# STM32L152.net
KiCad netlist of a schematic drawn in Altium Designer
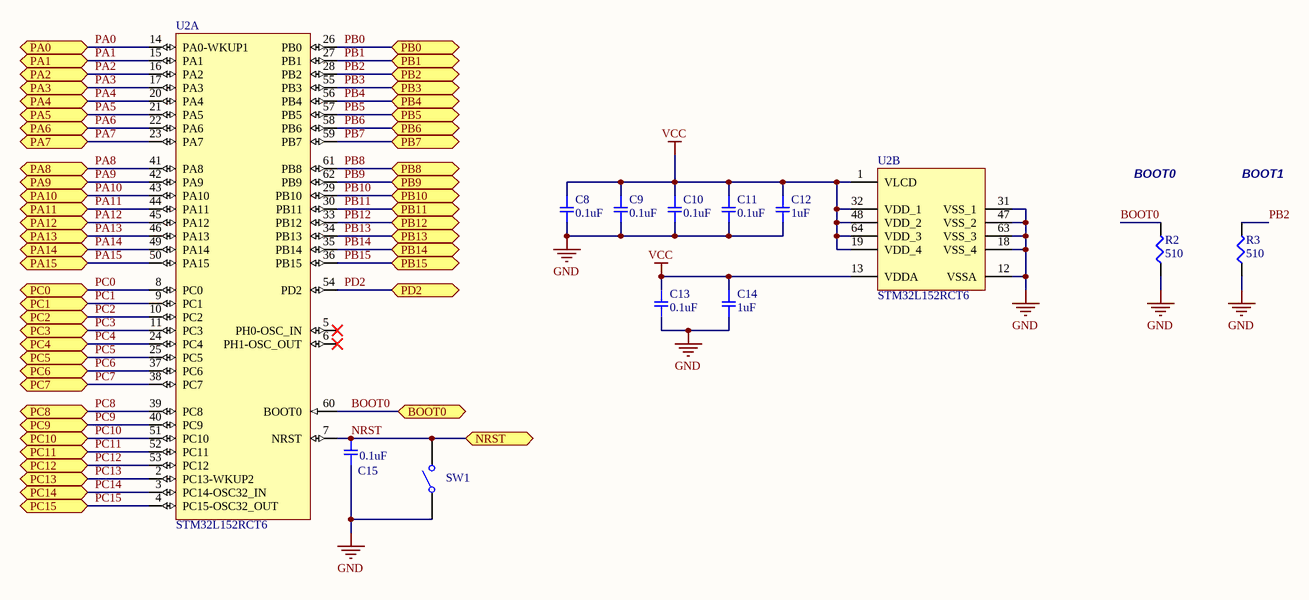
[diagram p0: STM32L152.SchDoc]

(export (version "E")
  (design (tool "Eeschema 10.0.6"))
  (components
    (comp (ref "C8")
      (value "0.1uF")
      (footprint "SMD-0805C")
      (description "CAP CER 0.1uF 50V X7T 0805")
      (fields
        (field (name "PART NUMBER") "GC321AD72E103KX01D")
        (field (name "MANUFACTURER") "Samsung Electro-Mechanics")
      )
      (libsource (lib "capacitor_0805") (part "CL21B104JBCNNNC"))
    )
    (comp (ref "C9")
      (value "0.1uF")
      (footprint "SMD-0805C")
      (description "CAP CER 0.1uF 50V X7T 0805")
      (fields
        (field (name "PART NUMBER") "GC321AD72E103KX01D")
        (field (name "MANUFACTURER") "Samsung Electro-Mechanics")
      )
      (libsource (lib "capacitor_0805") (part "CL21B104JBCNNNC"))
    )
    (comp (ref "C10")
      (value "0.1uF")
      (footprint "SMD-0805C")
      (description "CAP CER 0.1uF 50V X7T 0805")
      (fields
        (field (name "PART NUMBER") "GC321AD72E103KX01D")
        (field (name "MANUFACTURER") "Samsung Electro-Mechanics")
      )
      (libsource (lib "capacitor_0805") (part "CL21B104JBCNNNC"))
    )
    (comp (ref "C11")
      (value "0.1uF")
      (footprint "SMD-0805C")
      (description "CAP CER 0.1uF 50V X7T 0805")
      (fields
        (field (name "PART NUMBER") "GC321AD72E103KX01D")
        (field (name "MANUFACTURER") "Samsung Electro-Mechanics")
      )
      (libsource (lib "capacitor_0805") (part "CL21B104JBCNNNC"))
    )
    (comp (ref "C12")
      (value "1uF")
      (footprint "SMD-0805C")
      (description "CAP CER 1uF 16V X7T 0805")
      (fields
        (field (name "PART NUMBER") "CL21B105KOFNNNG")
        (field (name "MANUFACTURER") "Samsung Electro-Mechanics")
      )
      (libsource (lib "capacitor_0805") (part "CL21B105KOFNNNG"))
    )
    (comp (ref "C13")
      (value "0.1uF")
      (footprint "SMD-0805C")
      (description "CAP CER 0.1uF 50V X7T 0805")
      (fields
        (field (name "PART NUMBER") "GC321AD72E103KX01D")
        (field (name "MANUFACTURER") "Samsung Electro-Mechanics")
      )
      (libsource (lib "capacitor_0805") (part "CL21B104JBCNNNC"))
    )
    (comp (ref "C14")
      (value "1uF")
      (footprint "SMD-0805C")
      (description "CAP CER 1uF 16V X7T 0805")
      (fields
        (field (name "PART NUMBER") "CL21B105KOFNNNG")
        (field (name "MANUFACTURER") "Samsung Electro-Mechanics")
      )
      (libsource (lib "capacitor_0805") (part "CL21B105KOFNNNG"))
    )
    (comp (ref "C15")
      (value "0.1uF")
      (footprint "SMD-0805C")
      (description "CAP CER 0.1uF 50V X7T 0805")
      (fields
        (field (name "PART NUMBER") "GC321AD72E103KX01D")
        (field (name "MANUFACTURER") "Samsung Electro-Mechanics")
      )
      (libsource (lib "capacitor_0805") (part "CL21B104JBCNNNC"))
    )
    (comp (ref "R2")
      (value "510")
      (footprint "SMD-0805-RES")
      (description "RES SMD 510 OHM 5% 1/8W 0805")
      (fields (field (name "PART NUMBER") "ERJ-6GEYJ511V") (field (name "DIGI-KEY PART NUMBER") "P510ACT-ND"))
      (libsource (lib "Panasonic_ERJ_0805") (part "ERJ-6GEYJ511V"))
    )
    (comp (ref "R3")
      (value "510")
      (footprint "SMD-0805-RES")
      (description "RES SMD 510 OHM 5% 1/8W 0805")
      (fields (field (name "PART NUMBER") "ERJ-6GEYJ511V") (field (name "DIGI-KEY PART NUMBER") "P510ACT-ND"))
      (libsource (lib "Panasonic_ERJ_0805") (part "ERJ-6GEYJ511V"))
    )
    (comp (ref "SW1")
      (value "Switch_Tact")
      (footprint "Switch_Tact")
      (description "WS-TASV SMD Tact Switch 6.0X3.5 mm")
      (fields (field (name "PARTNUMBER") "434121050836"))
      (libsource (lib "Tesis") (part "Switch_Tact"))
    )
    (comp (ref "U2")
      (value "STM32L152RCT6")
      (footprint "STM-LQFP64_L")
      (fields (field (name "MANUFACTURER") "STMicroelectronics"))
      (libsource (lib "STMicroelectronics STM32 L1") (part "STM32L152RCT6"))
    )
  )
  (nets
    (net (code "1") (name "/BOOT0") (class "Default")
      (node (ref "R2") (pin "2") (pinfunction "2_2") (pintype "passive"))
      (node (ref "U2") (pin "60") (pinfunction "BOOT0_60") (pintype "input"))
    )
    (net (code "2") (name "/NRST") (class "Default")
      (node (ref "C15") (pin "1") (pinfunction "1_1") (pintype "passive"))
      (node (ref "SW1") (pin "2") (pinfunction "2_2") (pintype "passive"))
      (node (ref "U2") (pin "7") (pinfunction "NRST_7") (pintype "bidirectional"))
    )
    (net (code "3") (name "/PA0") (class "Default")
      (node (ref "U2") (pin "14") (pinfunction "PA0-WKUP1_14") (pintype "bidirectional"))
    )
    (net (code "4") (name "/PA1") (class "Default")
      (node (ref "U2") (pin "15") (pinfunction "PA1_15") (pintype "bidirectional"))
    )
    (net (code "5") (name "/PA2") (class "Default")
      (node (ref "U2") (pin "16") (pinfunction "PA2_16") (pintype "bidirectional"))
    )
    (net (code "6") (name "/PA3") (class "Default")
      (node (ref "U2") (pin "17") (pinfunction "PA3_17") (pintype "bidirectional"))
    )
    (net (code "7") (name "/PA4") (class "Default")
      (node (ref "U2") (pin "20") (pinfunction "PA4_20") (pintype "bidirectional"))
    )
    (net (code "8") (name "/PA5") (class "Default")
      (node (ref "U2") (pin "21") (pinfunction "PA5_21") (pintype "bidirectional"))
    )
    (net (code "9") (name "/PA6") (class "Default")
      (node (ref "U2") (pin "22") (pinfunction "PA6_22") (pintype "bidirectional"))
    )
    (net (code "10") (name "/PA7") (class "Default")
      (node (ref "U2") (pin "23") (pinfunction "PA7_23") (pintype "bidirectional"))
    )
    (net (code "11") (name "/PA8") (class "Default")
      (node (ref "U2") (pin "41") (pinfunction "PA8_41") (pintype "bidirectional"))
    )
    (net (code "12") (name "/PA9") (class "Default")
      (node (ref "U2") (pin "42") (pinfunction "PA9_42") (pintype "bidirectional"))
    )
    (net (code "13") (name "/PA10") (class "Default")
      (node (ref "U2") (pin "43") (pinfunction "PA10_43") (pintype "bidirectional"))
    )
    (net (code "14") (name "/PA11") (class "Default")
      (node (ref "U2") (pin "44") (pinfunction "PA11_44") (pintype "bidirectional"))
    )
    (net (code "15") (name "/PA12") (class "Default")
      (node (ref "U2") (pin "45") (pinfunction "PA12_45") (pintype "bidirectional"))
    )
    (net (code "16") (name "/PA13") (class "Default")
      (node (ref "U2") (pin "46") (pinfunction "PA13_46") (pintype "bidirectional"))
    )
    (net (code "17") (name "/PA14") (class "Default")
      (node (ref "U2") (pin "49") (pinfunction "PA14_49") (pintype "bidirectional"))
    )
    (net (code "18") (name "/PA15") (class "Default")
      (node (ref "U2") (pin "50") (pinfunction "PA15_50") (pintype "bidirectional"))
    )
    (net (code "19") (name "/PB0") (class "Default")
      (node (ref "U2") (pin "26") (pinfunction "PB0_26") (pintype "bidirectional"))
    )
    (net (code "20") (name "/PB1") (class "Default")
      (node (ref "U2") (pin "27") (pinfunction "PB1_27") (pintype "bidirectional"))
    )
    (net (code "21") (name "/PB2") (class "Default")
      (node (ref "R3") (pin "2") (pinfunction "2_2") (pintype "passive"))
      (node (ref "U2") (pin "28") (pinfunction "PB2_28") (pintype "bidirectional"))
    )
    (net (code "22") (name "/PB3") (class "Default")
      (node (ref "U2") (pin "55") (pinfunction "PB3_55") (pintype "bidirectional"))
    )
    (net (code "23") (name "/PB4") (class "Default")
      (node (ref "U2") (pin "56") (pinfunction "PB4_56") (pintype "bidirectional"))
    )
    (net (code "24") (name "/PB5") (class "Default")
      (node (ref "U2") (pin "57") (pinfunction "PB5_57") (pintype "bidirectional"))
    )
    (net (code "25") (name "/PB6") (class "Default")
      (node (ref "U2") (pin "58") (pinfunction "PB6_58") (pintype "bidirectional"))
    )
    (net (code "26") (name "/PB7") (class "Default")
      (node (ref "U2") (pin "59") (pinfunction "PB7_59") (pintype "bidirectional"))
    )
    (net (code "27") (name "/PB8") (class "Default")
      (node (ref "U2") (pin "61") (pinfunction "PB8_61") (pintype "bidirectional"))
    )
    (net (code "28") (name "/PB9") (class "Default")
      (node (ref "U2") (pin "62") (pinfunction "PB9_62") (pintype "bidirectional"))
    )
    (net (code "29") (name "/PB10") (class "Default")
      (node (ref "U2") (pin "29") (pinfunction "PB10_29") (pintype "bidirectional"))
    )
    (net (code "30") (name "/PB11") (class "Default")
      (node (ref "U2") (pin "30") (pinfunction "PB11_30") (pintype "bidirectional"))
    )
    (net (code "31") (name "/PB12") (class "Default")
      (node (ref "U2") (pin "33") (pinfunction "PB12_33") (pintype "bidirectional"))
    )
    (net (code "32") (name "/PB13") (class "Default")
      (node (ref "U2") (pin "34") (pinfunction "PB13_34") (pintype "bidirectional"))
    )
    (net (code "33") (name "/PB14") (class "Default")
      (node (ref "U2") (pin "35") (pinfunction "PB14_35") (pintype "bidirectional"))
    )
    (net (code "34") (name "/PB15") (class "Default")
      (node (ref "U2") (pin "36") (pinfunction "PB15_36") (pintype "bidirectional"))
    )
    (net (code "35") (name "/PC0") (class "Default")
      (node (ref "U2") (pin "8") (pinfunction "PC0_8") (pintype "bidirectional"))
    )
    (net (code "36") (name "/PC1") (class "Default")
      (node (ref "U2") (pin "9") (pinfunction "PC1_9") (pintype "bidirectional"))
    )
    (net (code "37") (name "/PC2") (class "Default")
      (node (ref "U2") (pin "10") (pinfunction "PC2_10") (pintype "bidirectional"))
    )
    (net (code "38") (name "/PC3") (class "Default")
      (node (ref "U2") (pin "11") (pinfunction "PC3_11") (pintype "bidirectional"))
    )
    (net (code "39") (name "/PC4") (class "Default")
      (node (ref "U2") (pin "24") (pinfunction "PC4_24") (pintype "bidirectional"))
    )
    (net (code "40") (name "/PC5") (class "Default")
      (node (ref "U2") (pin "25") (pinfunction "PC5_25") (pintype "bidirectional"))
    )
    (net (code "41") (name "/PC6") (class "Default")
      (node (ref "U2") (pin "37") (pinfunction "PC6_37") (pintype "bidirectional"))
    )
    (net (code "42") (name "/PC7") (class "Default")
      (node (ref "U2") (pin "38") (pinfunction "PC7_38") (pintype "bidirectional"))
    )
    (net (code "43") (name "/PC8") (class "Default")
      (node (ref "U2") (pin "39") (pinfunction "PC8_39") (pintype "bidirectional"))
    )
    (net (code "44") (name "/PC9") (class "Default")
      (node (ref "U2") (pin "40") (pinfunction "PC9_40") (pintype "bidirectional"))
    )
    (net (code "45") (name "/PC10") (class "Default")
      (node (ref "U2") (pin "51") (pinfunction "PC10_51") (pintype "bidirectional"))
    )
    (net (code "46") (name "/PC11") (class "Default")
      (node (ref "U2") (pin "52") (pinfunction "PC11_52") (pintype "bidirectional"))
    )
    (net (code "47") (name "/PC12") (class "Default")
      (node (ref "U2") (pin "53") (pinfunction "PC12_53") (pintype "bidirectional"))
    )
    (net (code "48") (name "/PC13") (class "Default")
      (node (ref "U2") (pin "2") (pinfunction "PC13-WKUP2_2") (pintype "bidirectional"))
    )
    (net (code "49") (name "/PC14") (class "Default")
      (node (ref "U2") (pin "3") (pinfunction "PC14-OSC32_IN_3") (pintype "bidirectional"))
    )
    (net (code "50") (name "/PC15") (class "Default")
      (node (ref "U2") (pin "4") (pinfunction "PC15-OSC32_OUT_4") (pintype "bidirectional"))
    )
    (net (code "51") (name "/PD2") (class "Default")
      (node (ref "U2") (pin "54") (pinfunction "PD2_54") (pintype "bidirectional"))
    )
    (net (code "52") (name "GND") (class "Default")
      (node (ref "C10") (pin "2") (pinfunction "2_2") (pintype "passive"))
      (node (ref "C11") (pin "2") (pinfunction "2_2") (pintype "passive"))
      (node (ref "C12") (pin "2") (pinfunction "2_2") (pintype "passive"))
      (node (ref "C13") (pin "2") (pinfunction "2_2") (pintype "passive"))
      (node (ref "C14") (pin "2") (pinfunction "2_2") (pintype "passive"))
      (node (ref "C15") (pin "2") (pinfunction "2_2") (pintype "passive"))
      (node (ref "C8") (pin "2") (pinfunction "2_2") (pintype "passive"))
      (node (ref "C9") (pin "2") (pinfunction "2_2") (pintype "passive"))
      (node (ref "R2") (pin "1") (pinfunction "1_1") (pintype "passive"))
      (node (ref "R3") (pin "1") (pinfunction "1_1") (pintype "passive"))
      (node (ref "SW1") (pin "1") (pinfunction "1_1") (pintype "passive"))
      (node (ref "U2") (pin "12") (pinfunction "VSSA_12") (pintype "power_in"))
      (node (ref "U2") (pin "18") (pinfunction "VSS_4_18") (pintype "power_in"))
      (node (ref "U2") (pin "31") (pinfunction "VSS_1_31") (pintype "power_in"))
      (node (ref "U2") (pin "47") (pinfunction "VSS_2_47") (pintype "power_in"))
      (node (ref "U2") (pin "63") (pinfunction "VSS_3_63") (pintype "power_in"))
    )
    (net (code "53") (name "VCC") (class "Default")
      (node (ref "C10") (pin "1") (pinfunction "1_1") (pintype "passive"))
      (node (ref "C11") (pin "1") (pinfunction "1_1") (pintype "passive"))
      (node (ref "C12") (pin "1") (pinfunction "1_1") (pintype "passive"))
      (node (ref "C13") (pin "1") (pinfunction "1_1") (pintype "passive"))
      (node (ref "C14") (pin "1") (pinfunction "1_1") (pintype "passive"))
      (node (ref "C8") (pin "1") (pinfunction "1_1") (pintype "passive"))
      (node (ref "C9") (pin "1") (pinfunction "1_1") (pintype "passive"))
      (node (ref "U2") (pin "1") (pinfunction "VLCD_1") (pintype "power_in"))
      (node (ref "U2") (pin "13") (pinfunction "VDDA_13") (pintype "power_in"))
      (node (ref "U2") (pin "19") (pinfunction "VDD_4_19") (pintype "power_in"))
      (node (ref "U2") (pin "32") (pinfunction "VDD_1_32") (pintype "power_in"))
      (node (ref "U2") (pin "48") (pinfunction "VDD_2_48") (pintype "power_in"))
      (node (ref "U2") (pin "64") (pinfunction "VDD_3_64") (pintype "power_in"))
    )
    (net (code "54") (name "unconnected-(U2A-PH0-OSC_IN-Pad5)") (class "Default")
      (node (ref "U2") (pin "5") (pinfunction "PH0-OSC_IN_5") (pintype "bidirectional+no_connect"))
    )
    (net (code "55") (name "unconnected-(U2A-PH1-OSC_OUT-Pad6)") (class "Default")
      (node (ref "U2") (pin "6") (pinfunction "PH1-OSC_OUT_6") (pintype "bidirectional+no_connect"))
    )
  )
)
